# yyb_v2_5_sensor.net
KiCad netlist of a schematic drawn in Altium Designer
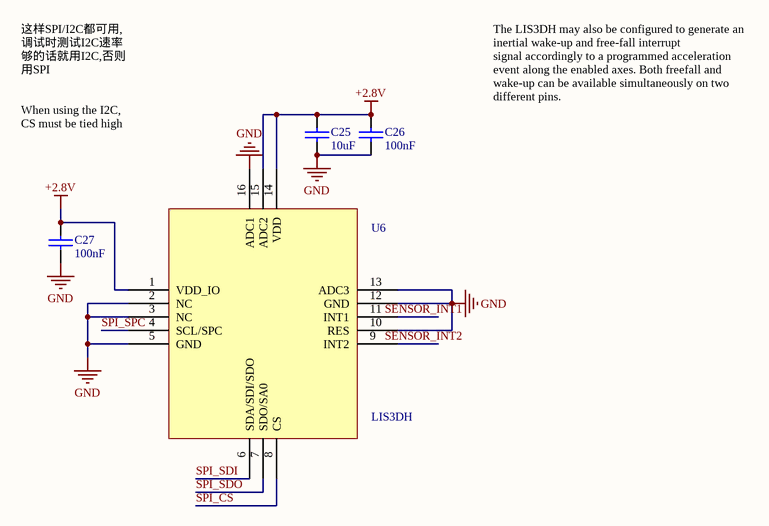
[diagram p0: yyb_v2.5_sensor.SchDoc]

(export (version "E")
  (design (tool "Eeschema 10.0.6"))
  (components
    (comp (ref "C25")
      (value "10uF")
      (footprint "0603C")
      (description "Capacitor")
      (libsource (lib "*") (part "CAP"))
    )
    (comp (ref "C26")
      (value "100nF")
      (footprint "0603C")
      (description "Capacitor")
      (libsource (lib "*") (part "CAP"))
    )
    (comp (ref "C27")
      (value "100nF")
      (footprint "0603C")
      (description "Capacitor")
      (libsource (lib "*") (part "CAP"))
    )
    (comp (ref "U6")
      (value "LIS3DH")
      (footprint "LGA16R50P7X5_300X300X100")
      (libsource (lib "Schlib1") (part "LIS3DH"))
    )
  )
  (nets
    (net (code "1") (name "+2.8V") (class "Default")
      (node (ref "C25") (pin "1") (pinfunction "1_1") (pintype "passive"))
      (node (ref "C26") (pin "1") (pinfunction "1_1") (pintype "passive"))
      (node (ref "C27") (pin "1") (pinfunction "1_1") (pintype "passive"))
      (node (ref "U6") (pin "1") (pinfunction "VDD_IO_1") (pintype "passive"))
      (node (ref "U6") (pin "14") (pinfunction "VDD_14") (pintype "passive"))
      (node (ref "U6") (pin "15") (pinfunction "ADC2_15") (pintype "passive"))
    )
    (net (code "4") (name "/SPI_CS") (class "Default")
      (node (ref "U6") (pin "8") (pinfunction "CS_8") (pintype "passive"))
    )
    (net (code "5") (name "/SPI_SDI") (class "Default")
      (node (ref "U6") (pin "6") (pinfunction "SDA/SDI/SDO_6") (pintype "passive"))
    )
    (net (code "6") (name "/SPI_SDO") (class "Default")
      (node (ref "U6") (pin "7") (pinfunction "SDO/SA0_7") (pintype "passive"))
    )
    (net (code "7") (name "/SPI_SPC") (class "Default")
      (node (ref "U6") (pin "4") (pinfunction "SCL/SPC_4") (pintype "passive"))
    )
    (net (code "8") (name "GND") (class "Default")
      (node (ref "C25") (pin "2") (pinfunction "2_2") (pintype "passive"))
      (node (ref "C26") (pin "2") (pinfunction "2_2") (pintype "passive"))
      (node (ref "C27") (pin "2") (pinfunction "2_2") (pintype "passive"))
      (node (ref "U6") (pin "10") (pinfunction "RES_10") (pintype "passive"))
      (node (ref "U6") (pin "12") (pinfunction "GND_12") (pintype "passive"))
      (node (ref "U6") (pin "13") (pinfunction "ADC3_13") (pintype "passive"))
      (node (ref "U6") (pin "16") (pinfunction "ADC1_16") (pintype "passive"))
      (node (ref "U6") (pin "2") (pinfunction "NC_2") (pintype "passive"))
      (node (ref "U6") (pin "3") (pinfunction "NC_3") (pintype "passive"))
      (node (ref "U6") (pin "5") (pinfunction "GND_5") (pintype "passive"))
    )
    (net (code "9") (name "unconnected-(U6-INT1-Pad11)") (class "Default")
      (node (ref "U6") (pin "11") (pinfunction "INT1_11") (pintype "passive"))
    )
    (net (code "10") (name "unconnected-(U6-INT2-Pad9)") (class "Default")
      (node (ref "U6") (pin "9") (pinfunction "INT2_9") (pintype "passive"))
    )
  )
)
